# sensors.net
KiCad netlist of a schematic drawn in Altium Designer
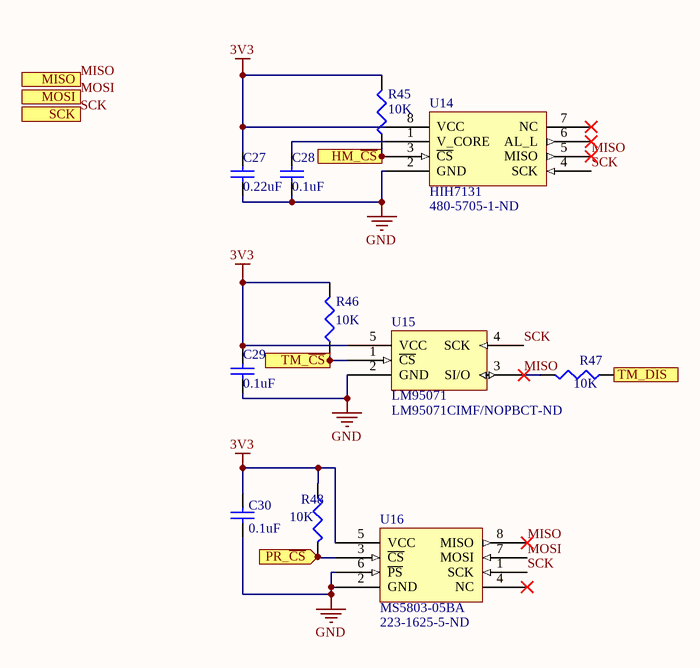
[diagram p0: sensors.SchDoc]

(export (version "E")
  (design (tool "Eeschema 10.0.6"))
  (components
    (comp (ref "C27")
      (value "0.22uF")
      (footprint "1608[0603]")
      (description "Capacitor (Semiconductor SIM Model)")
      (fields (field (name "PUBLISHER") "Altium Limited"))
      (libsource (lib "Miscellaneous Devices") (part "Cap Semi"))
    )
    (comp (ref "C28")
      (value "0.1uF")
      (footprint "1608[0603]")
      (description "Capacitor (Semiconductor SIM Model)")
      (fields (field (name "PUBLISHER") "Altium Limited"))
      (libsource (lib "Miscellaneous Devices") (part "Cap Semi"))
    )
    (comp (ref "C29")
      (value "0.1uF")
      (footprint "1608[0603]")
      (description "Capacitor (Semiconductor SIM Model)")
      (fields (field (name "PUBLISHER") "Altium Limited"))
      (libsource (lib "Miscellaneous Devices") (part "Cap Semi"))
    )
    (comp (ref "C30")
      (value "0.1uF")
      (footprint "1608[0603]")
      (description "Capacitor (Semiconductor SIM Model)")
      (fields (field (name "PUBLISHER") "Altium Limited"))
      (libsource (lib "Miscellaneous Devices") (part "Cap Semi"))
    )
    (comp (ref "R45")
      (value "10K")
      (footprint "J1-0603")
      (description "Resistor")
      (fields (field (name "PUBLISHER") "Altium Limited"))
      (libsource (lib "Miscellaneous Devices") (part "Res3"))
    )
    (comp (ref "R46")
      (value "10K")
      (footprint "J1-0603")
      (description "Resistor")
      (fields (field (name "PUBLISHER") "Altium Limited"))
      (libsource (lib "Miscellaneous Devices") (part "Res3"))
    )
    (comp (ref "R47")
      (value "10K")
      (footprint "J1-0603")
      (description "Resistor")
      (fields (field (name "PUBLISHER") "Altium Limited"))
      (libsource (lib "Miscellaneous Devices") (part "Res3"))
    )
    (comp (ref "R48")
      (value "10K")
      (footprint "J1-0603")
      (description "Resistor")
      (fields (field (name "PUBLISHER") "Altium Limited"))
      (libsource (lib "Miscellaneous Devices") (part "Res3"))
    )
    (comp (ref "U14")
      (value "HIH7131")
      (footprint "SOIC127P500X600-8N")
      (fields (field (name "SUPPLIER PART NUMBER 1") "480-5705-1-ND"))
      (libsource (lib "PAY") (part "HIH7131"))
    )
    (comp (ref "U15")
      (value "LM95071")
      (footprint "SOT-23-5_95P290X160-5N")
      (description "13 bit plus sign digital temperature sensor. Nominal +/- 1 C accuracy from 0-70 C.")
      (fields (field (name "SUPPLIER PART NUMBER 1") "LM95071CIMF/NOPBCT-ND"))
      (libsource (lib "PAY") (part "LM95071"))
    )
    (comp (ref "U16")
      (value "MS5803-05BA")
      (footprint "MS5803-05BA_125P640x620-8N")
      (fields (field (name "SUPPLIER PART NUMBER 1") "223-1625-5-ND"))
      (libsource (lib "PAY") (part "MS5803-05BA"))
    )
  )
  (nets
    (net (code "1") (name "/HM_~{CS}") (class "Default")
      (node (ref "R45") (pin "1") (pinfunction "1_1") (pintype "passive"))
      (node (ref "U14") (pin "3") (pinfunction "~{CS}_3") (pintype "input"))
    )
    (net (code "2") (name "/MISO") (class "Default")
      (node (ref "R47") (pin "2") (pinfunction "2_2") (pintype "passive"))
      (node (ref "U14") (pin "5") (pinfunction "MISO_5") (pintype "output"))
      (node (ref "U15") (pin "3") (pinfunction "SI/O_3") (pintype "bidirectional"))
      (node (ref "U16") (pin "8") (pinfunction "MISO_8") (pintype "output"))
    )
    (net (code "3") (name "/MOSI") (class "Default")
      (node (ref "U16") (pin "7") (pinfunction "MOSI_7") (pintype "input"))
    )
    (net (code "4") (name "/PR_~{CS}") (class "Default")
      (node (ref "R48") (pin "2") (pinfunction "2_2") (pintype "passive"))
      (node (ref "U16") (pin "3") (pinfunction "~{CS}_3") (pintype "input"))
    )
    (net (code "5") (name "/SCK") (class "Default")
      (node (ref "U14") (pin "4") (pinfunction "SCK_4") (pintype "input"))
      (node (ref "U15") (pin "4") (pinfunction "SCK_4") (pintype "input"))
      (node (ref "U16") (pin "1") (pinfunction "SCK_1") (pintype "input"))
    )
    (net (code "6") (name "/TM_DIS") (class "Default")
      (node (ref "R47") (pin "1") (pinfunction "1_1") (pintype "passive"))
    )
    (net (code "7") (name "/TM_~{CS}") (class "Default")
      (node (ref "R46") (pin "1") (pinfunction "1_1") (pintype "passive"))
      (node (ref "U15") (pin "1") (pinfunction "~{CS}_1") (pintype "input"))
    )
    (net (code "8") (name "3V3") (class "Default")
      (node (ref "C27") (pin "2") (pinfunction "2_2") (pintype "passive"))
      (node (ref "C29") (pin "2") (pinfunction "2_2") (pintype "passive"))
      (node (ref "C30") (pin "2") (pinfunction "2_2") (pintype "passive"))
      (node (ref "R45") (pin "2") (pinfunction "2_2") (pintype "passive"))
      (node (ref "R46") (pin "2") (pinfunction "2_2") (pintype "passive"))
      (node (ref "R48") (pin "1") (pinfunction "1_1") (pintype "passive"))
      (node (ref "U14") (pin "8") (pinfunction "VCC_8") (pintype "power_in"))
      (node (ref "U15") (pin "5") (pinfunction "VCC_5") (pintype "power_in"))
      (node (ref "U16") (pin "5") (pinfunction "VCC_5") (pintype "power_in"))
    )
    (net (code "9") (name "GND") (class "Default")
      (node (ref "C27") (pin "1") (pinfunction "1_1") (pintype "passive"))
      (node (ref "C28") (pin "1") (pinfunction "1_1") (pintype "passive"))
      (node (ref "C29") (pin "1") (pinfunction "1_1") (pintype "passive"))
      (node (ref "C30") (pin "1") (pinfunction "1_1") (pintype "passive"))
      (node (ref "U14") (pin "2") (pinfunction "GND_2") (pintype "power_in"))
      (node (ref "U15") (pin "2") (pinfunction "GND_2") (pintype "power_in"))
      (node (ref "U16") (pin "2") (pinfunction "GND_2") (pintype "power_in"))
      (node (ref "U16") (pin "6") (pinfunction "~{PS}_6") (pintype "input"))
    )
    (net (code "10") (name "Net-(U14-V_CORE)") (class "Default")
      (node (ref "C28") (pin "2") (pinfunction "2_2") (pintype "passive"))
      (node (ref "U14") (pin "1") (pinfunction "V_CORE_1") (pintype "power_in"))
    )
    (net (code "11") (name "unconnected-(U14-AL_L-Pad6)") (class "Default")
      (node (ref "U14") (pin "6") (pinfunction "AL_L_6") (pintype "output+no_connect"))
    )
    (net (code "12") (name "unconnected-(U14-NC-Pad7)") (class "Default")
      (node (ref "U14") (pin "7") (pinfunction "NC_7") (pintype "passive+no_connect"))
    )
    (net (code "13") (name "unconnected-(U16-NC-Pad4)") (class "Default")
      (node (ref "U16") (pin "4") (pinfunction "NC_4") (pintype "passive+no_connect"))
    )
  )
)
